# 6_clock.net
KiCad netlist of a schematic drawn in Altium Designer
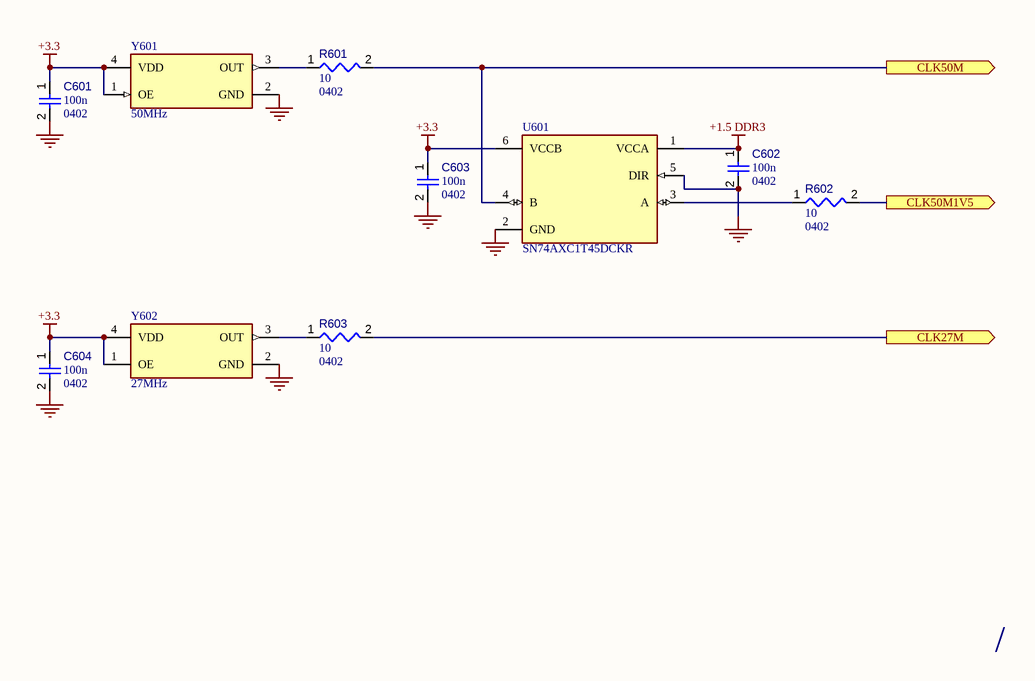
[diagram p0: 6 clock.SchDoc]

(export (version "E")
  (design (tool "Eeschema 10.0.6"))
  (components
    (comp (ref "C601")
      (value "100n")
      (footprint "CAPC0402(1005)60_L")
      (description "Capacitor")
      (fields (field (name "CASE/PACKAGE") "0402") (field (name "Comment") "Capacitors,0402,100n,16"))
      (libsource (lib "UBC Uncrewed Aircraft Systems") (part "CAP-NP-2"))
    )
    (comp (ref "C602")
      (value "100n")
      (footprint "CAPC0402(1005)60_L")
      (description "Capacitor")
      (fields (field (name "CASE/PACKAGE") "0402") (field (name "Comment") "Capacitors,0402,100n,16"))
      (libsource (lib "UBC Uncrewed Aircraft Systems") (part "CAP-NP-2"))
    )
    (comp (ref "C603")
      (value "100n")
      (footprint "CAPC0402(1005)60_L")
      (description "Capacitor")
      (fields (field (name "CASE/PACKAGE") "0402") (field (name "Comment") "Capacitors,0402,100n,16"))
      (libsource (lib "UBC Uncrewed Aircraft Systems") (part "CAP-NP-2"))
    )
    (comp (ref "C604")
      (value "100n")
      (footprint "CAPC0402(1005)60_L")
      (description "Capacitor")
      (fields (field (name "CASE/PACKAGE") "0402") (field (name "Comment") "Capacitors,0402,100n,16"))
      (libsource (lib "UBC Uncrewed Aircraft Systems") (part "CAP-NP-2"))
    )
    (comp (ref "R601")
      (value "10")
      (footprint "RESC0402(1005)_L")
      (description "Resistor")
      (fields (field (name "CASE/PACKAGE") "0402") (field (name "Comment") "Resistors,0402,10"))
      (libsource (lib "UBC Uncrewed Aircraft Systems") (part "RES-2"))
    )
    (comp (ref "R602")
      (value "10")
      (footprint "RESC0402(1005)_L")
      (description "Resistor")
      (fields (field (name "CASE/PACKAGE") "0402") (field (name "Comment") "Resistors,0402,10"))
      (libsource (lib "UBC Uncrewed Aircraft Systems") (part "RES-2"))
    )
    (comp (ref "R603")
      (value "10")
      (footprint "RESC0402(1005)_L")
      (description "Resistor")
      (fields (field (name "CASE/PACKAGE") "0402") (field (name "Comment") "Resistors,0402,10"))
      (libsource (lib "UBC Uncrewed Aircraft Systems") (part "RES-2"))
    )
    (comp (ref "U601")
      (value "SN74AXC1T45DCKR")
      (footprint "FP-DCK0006A-MFG")
      (description "IC TRNSLTR BIDIRECTIONAL SC70-6")
      (libsource (lib "Altium Content Vault") (part "d0dbdffe323aa12037fe7fb072119e8"))
    )
    (comp (ref "Y601")
      (value "SIT8008BI-23-33E-50.000000E")
      (footprint "FP-SiT8008-2-MFG")
      (description "50 MHz XO (Standard) HCMOS, LVCMOS Oscillator 3.3V Enable/Disable 4-SMD, No Lead")
      (fields (field (name "FREQUENCY") "50MHz"))
      (libsource (lib "Altium Content Vault") (part "ab5556b3551095060e619687c253883"))
    )
    (comp (ref "Y602")
      (value "SIT8208AI-2F-33E-27.000000Y")
      (footprint "FP-SiT8208-2-MFG")
      (description "MEMS OSC XO 27.0000MHZ LVCMOS LV")
      (fields (field (name "FREQUENCY") "27MHz"))
      (libsource (lib "Altium Content Vault") (part "fa3a2c73a39c6b740c8d7d56d90039b"))
    )
  )
  (nets
    (net (code "1") (name "+1.5 DDR3") (class "Default")
      (node (ref "C602") (pin "1") (pinfunction "1_1") (pintype "passive"))
      (node (ref "U601") (pin "1") (pinfunction "VCCA_1") (pintype "power_in"))
    )
    (net (code "2") (name "+3.3") (class "Default")
      (node (ref "C601") (pin "1") (pinfunction "1_1") (pintype "passive"))
      (node (ref "C603") (pin "1") (pinfunction "1_1") (pintype "passive"))
      (node (ref "C604") (pin "1") (pinfunction "1_1") (pintype "passive"))
      (node (ref "U601") (pin "6") (pinfunction "VCCB_6") (pintype "power_in"))
      (node (ref "Y601") (pin "1") (pinfunction "OE_1") (pintype "input"))
      (node (ref "Y601") (pin "4") (pinfunction "VDD_4") (pintype "power_in"))
      (node (ref "Y602") (pin "1") (pinfunction "OE_1") (pintype "passive"))
      (node (ref "Y602") (pin "4") (pinfunction "VDD_4") (pintype "power_in"))
    )
    (net (code "3") (name "/CLK27M") (class "Default")
      (node (ref "R603") (pin "2") (pinfunction "2_2") (pintype "passive"))
    )
    (net (code "4") (name "/CLK50M") (class "Default")
      (node (ref "R601") (pin "2") (pinfunction "2_2") (pintype "passive"))
      (node (ref "U601") (pin "4") (pinfunction "B_4") (pintype "bidirectional"))
    )
    (net (code "5") (name "/CLK50M1V5") (class "Default")
      (node (ref "R602") (pin "2") (pinfunction "2_2") (pintype "passive"))
    )
    (net (code "6") (name "GND") (class "Default")
      (node (ref "C601") (pin "2") (pinfunction "2_2") (pintype "passive"))
      (node (ref "C602") (pin "2") (pinfunction "2_2") (pintype "passive"))
      (node (ref "C603") (pin "2") (pinfunction "2_2") (pintype "passive"))
      (node (ref "C604") (pin "2") (pinfunction "2_2") (pintype "passive"))
      (node (ref "U601") (pin "2") (pinfunction "GND_2") (pintype "power_in"))
      (node (ref "U601") (pin "5") (pinfunction "DIR_5") (pintype "input"))
      (node (ref "Y601") (pin "2") (pinfunction "GND_2") (pintype "power_in"))
      (node (ref "Y602") (pin "2") (pinfunction "GND_2") (pintype "power_in"))
    )
    (net (code "7") (name "Net-(U601-A)") (class "Default")
      (node (ref "R602") (pin "1") (pinfunction "1_1") (pintype "passive"))
      (node (ref "U601") (pin "3") (pinfunction "A_3") (pintype "bidirectional"))
    )
    (net (code "8") (name "Net-(Y601-OUT)") (class "Default")
      (node (ref "R601") (pin "1") (pinfunction "1_1") (pintype "passive"))
      (node (ref "Y601") (pin "3") (pinfunction "OUT_3") (pintype "output"))
    )
    (net (code "9") (name "Net-(Y602-OUT)") (class "Default")
      (node (ref "R603") (pin "1") (pinfunction "1_1") (pintype "passive"))
      (node (ref "Y602") (pin "3") (pinfunction "OUT_3") (pintype "output"))
    )
  )
)
